# 04_POWER.net
KiCad netlist of a schematic drawn in Altium Designer
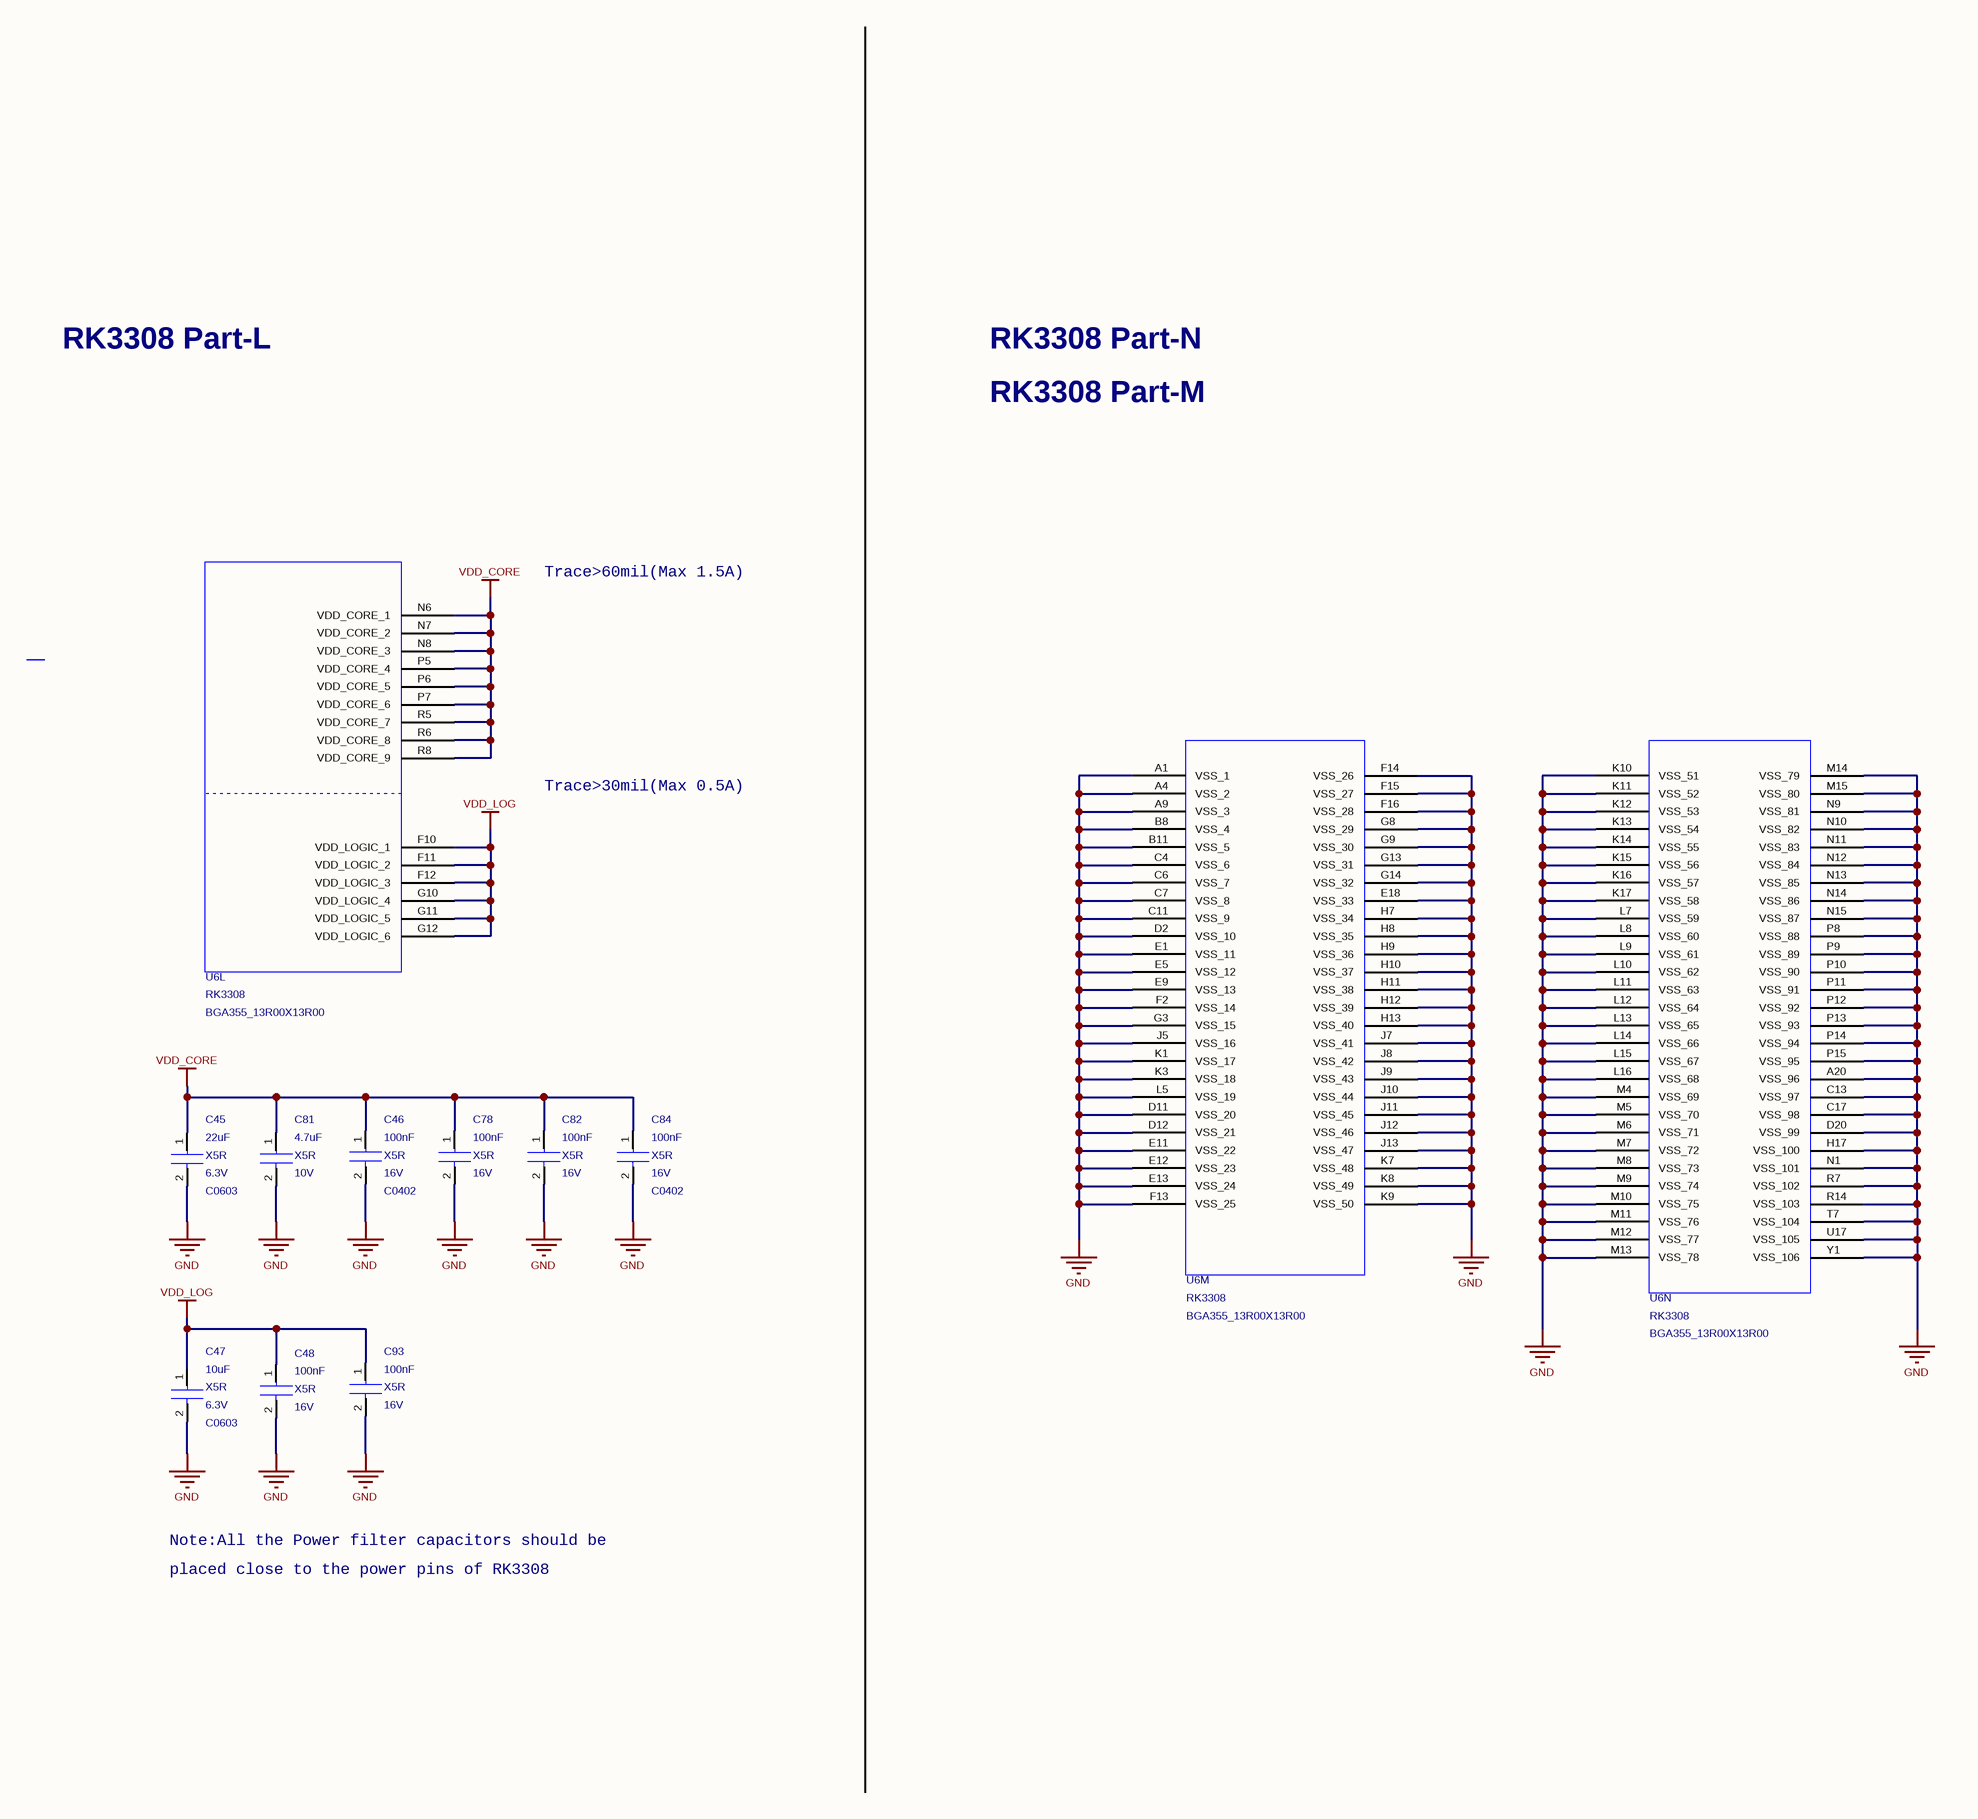
[diagram p0: 04_POWER.SchDoc]

(export (version "E")
  (design (tool "Eeschema 10.0.6"))
  (components
    (comp (ref "C45")
      (value "22uF")
      (footprint "C0603")
      (description "cap,22.00uF,+/-20%,6.3V,X5R,C0603")
      (fields
        (field (name "PCB DECAL") "C0603")
        (field (name "MANUFACTURER") "TDK")
        (field (name "TOLERANCE") "20%")
        (field (name "VOLTAGE") "6.3V")
        (field (name "DIELECTRIC") "X5R")
        (field (name "CREATED_BY") "JJJ")
      )
      (libsource (lib "*") (part "CAP_NP_2"))
    )
    (comp (ref "C46")
      (value "100nF")
      (footprint "C0402")
      (description "cap,100.00nF,+/-10%,16V,X5R,C0402")
      (fields
        (field (name "PCB DECAL") "C0402")
        (field (name "MANUFACTURER") "TDK")
        (field (name "TOLERANCE") "10%")
        (field (name "VOLTAGE") "16V")
        (field (name "DIELECTRIC") "X5R")
        (field (name "CREATED_BY") "JJJ")
      )
      (libsource (lib "*") (part "CAP_NP_2"))
    )
    (comp (ref "C47")
      (value "10uF")
      (footprint "C0603")
      (description "cap,10.00uF,+/-10%,6.3V,X5R,C0603")
      (fields
        (field (name "PCB DECAL") "C0603")
        (field (name "MANUFACTURER") "TDK")
        (field (name "TOLERANCE") "10%")
        (field (name "VOLTAGE") "6.3V")
        (field (name "DIELECTRIC") "X5R")
        (field (name "CREATED_BY") "JJJ")
      )
      (libsource (lib "*") (part "CAP_NP_2"))
    )
    (comp (ref "C48")
      (value "100nF")
      (footprint "C0402")
      (description "cap,100.00nF,+/-10%,16V,X5R,C0402")
      (fields
        (field (name "DIELECTRIC") "X5R")
        (field (name "VOLTAGE") "16V")
        (field (name "TOLERANCE") "10%")
        (field (name "MANUFACTURER") "TDK")
        (field (name "CREATED_BY") "JJJ")
      )
      (libsource (lib "*") (part "CAP_NP_2"))
    )
    (comp (ref "C78")
      (value "100nF")
      (footprint "C0402")
      (description "cap,100.00nF,+/-10%,16V,X5R,C0402")
      (fields
        (field (name "DIELECTRIC") "X5R")
        (field (name "VOLTAGE") "16V")
        (field (name "TOLERANCE") "10%")
        (field (name "MANUFACTURER") "TDK")
        (field (name "CREATED_BY") "JJJ")
      )
      (libsource (lib "*") (part "CAP_NP_2"))
    )
    (comp (ref "C81")
      (value "4.7uF")
      (footprint "C0402")
      (description "cap,4.70uF,+/-10%,10V,X5R,C0402")
      (fields
        (field (name "DIELECTRIC") "X5R")
        (field (name "VOLTAGE") "10V")
        (field (name "TOLERANCE") "10%")
        (field (name "MANUFACTURER") "TDK")
        (field (name "CREATED_BY") "JJJ")
      )
      (libsource (lib "*") (part "CAP_NP_2"))
    )
    (comp (ref "C82")
      (value "100nF")
      (footprint "C0402")
      (description "cap,100.00nF,+/-10%,16V,X5R,C0402")
      (fields
        (field (name "MANUFACTURER") "TDK")
        (field (name "TOLERANCE") "10%")
        (field (name "VOLTAGE") "16V")
        (field (name "DIELECTRIC") "X5R")
        (field (name "CREATED_BY") "JJJ")
      )
      (libsource (lib "*") (part "CAP_NP_2"))
    )
    (comp (ref "C84")
      (value "100nF")
      (footprint "C0402")
      (description "cap,100.00nF,+/-10%,16V,X5R,C0402")
      (fields
        (field (name "PCB DECAL") "C0402")
        (field (name "DIELECTRIC") "X5R")
        (field (name "VOLTAGE") "16V")
        (field (name "TOLERANCE") "10%")
        (field (name "MANUFACTURER") "TDK")
        (field (name "CREATED_BY") "JJJ")
      )
      (libsource (lib "*") (part "CAP_NP_2"))
    )
    (comp (ref "C93")
      (value "100nF")
      (footprint "C0402")
      (description "cap,100.00nF,+/-10%,16V,X5R,C0402")
      (fields
        (field (name "DIELECTRIC") "X5R")
        (field (name "VOLTAGE") "16V")
        (field (name "TOLERANCE") "10%")
        (field (name "MANUFACTURER") "TDK")
        (field (name "CREATED_BY") "JJJ")
      )
      (libsource (lib "*") (part "CAP_NP_2"))
    )
    (comp (ref "U6")
      (value "RK3308")
      (footprint "BGA355_13R00X13R00")
      (fields (field (name "PCB DECAL") "BGA355_13R00X13R00") (field (name "MANUFACTURER") "ROCKCHIP"))
      (libsource (lib "*") (part "RK3308"))
    )
  )
  (nets
    (net (code "1") (name "GND") (class "Default")
      (node (ref "C45") (pin "2") (pinfunction "2_2") (pintype "passive"))
      (node (ref "C46") (pin "2") (pinfunction "2_2") (pintype "passive"))
      (node (ref "C47") (pin "2") (pinfunction "2_2") (pintype "passive"))
      (node (ref "C48") (pin "2") (pinfunction "2_2") (pintype "passive"))
      (node (ref "C78") (pin "2") (pinfunction "2_2") (pintype "passive"))
      (node (ref "C81") (pin "2") (pinfunction "2_2") (pintype "passive"))
      (node (ref "C82") (pin "2") (pinfunction "2_2") (pintype "passive"))
      (node (ref "C84") (pin "2") (pinfunction "2_2") (pintype "passive"))
      (node (ref "C93") (pin "2") (pinfunction "2_2") (pintype "passive"))
      (node (ref "U6") (pin "A1") (pinfunction "VSS_1_A1") (pintype "power_in"))
      (node (ref "U6") (pin "A20") (pinfunction "VSS_96_A20") (pintype "power_in"))
      (node (ref "U6") (pin "A4") (pinfunction "VSS_2_A4") (pintype "power_in"))
      (node (ref "U6") (pin "A9") (pinfunction "VSS_3_A9") (pintype "power_in"))
      (node (ref "U6") (pin "B11") (pinfunction "VSS_5_B11") (pintype "power_in"))
      (node (ref "U6") (pin "B8") (pinfunction "VSS_4_B8") (pintype "power_in"))
      (node (ref "U6") (pin "C11") (pinfunction "VSS_9_C11") (pintype "power_in"))
      (node (ref "U6") (pin "C13") (pinfunction "VSS_97_C13") (pintype "power_in"))
      (node (ref "U6") (pin "C17") (pinfunction "VSS_98_C17") (pintype "power_in"))
      (node (ref "U6") (pin "C4") (pinfunction "VSS_6_C4") (pintype "power_in"))
      (node (ref "U6") (pin "C6") (pinfunction "VSS_7_C6") (pintype "power_in"))
      (node (ref "U6") (pin "C7") (pinfunction "VSS_8_C7") (pintype "power_in"))
      (node (ref "U6") (pin "D11") (pinfunction "VSS_20_D11") (pintype "power_in"))
      (node (ref "U6") (pin "D12") (pinfunction "VSS_21_D12") (pintype "power_in"))
      (node (ref "U6") (pin "D2") (pinfunction "VSS_10_D2") (pintype "power_in"))
      (node (ref "U6") (pin "D20") (pinfunction "VSS_99_D20") (pintype "power_in"))
      (node (ref "U6") (pin "E1") (pinfunction "VSS_11_E1") (pintype "power_in"))
      (node (ref "U6") (pin "E11") (pinfunction "VSS_22_E11") (pintype "power_in"))
      (node (ref "U6") (pin "E12") (pinfunction "VSS_23_E12") (pintype "power_in"))
      (node (ref "U6") (pin "E13") (pinfunction "VSS_24_E13") (pintype "power_in"))
      (node (ref "U6") (pin "E18") (pinfunction "VSS_33_E18") (pintype "power_in"))
      (node (ref "U6") (pin "E5") (pinfunction "VSS_12_E5") (pintype "power_in"))
      (node (ref "U6") (pin "E9") (pinfunction "VSS_13_E9") (pintype "power_in"))
      (node (ref "U6") (pin "F13") (pinfunction "VSS_25_F13") (pintype "power_in"))
      (node (ref "U6") (pin "F14") (pinfunction "VSS_26_F14") (pintype "power_in"))
      (node (ref "U6") (pin "F15") (pinfunction "VSS_27_F15") (pintype "power_in"))
      (node (ref "U6") (pin "F16") (pinfunction "VSS_28_F16") (pintype "power_in"))
      (node (ref "U6") (pin "F2") (pinfunction "VSS_14_F2") (pintype "power_in"))
      (node (ref "U6") (pin "G13") (pinfunction "VSS_31_G13") (pintype "power_in"))
      (node (ref "U6") (pin "G14") (pinfunction "VSS_32_G14") (pintype "power_in"))
      (node (ref "U6") (pin "G3") (pinfunction "VSS_15_G3") (pintype "power_in"))
      (node (ref "U6") (pin "G8") (pinfunction "VSS_29_G8") (pintype "power_in"))
      (node (ref "U6") (pin "G9") (pinfunction "VSS_30_G9") (pintype "power_in"))
      (node (ref "U6") (pin "H10") (pinfunction "VSS_37_H10") (pintype "power_in"))
      (node (ref "U6") (pin "H11") (pinfunction "VSS_38_H11") (pintype "power_in"))
      (node (ref "U6") (pin "H12") (pinfunction "VSS_39_H12") (pintype "power_in"))
      (node (ref "U6") (pin "H13") (pinfunction "VSS_40_H13") (pintype "power_in"))
      (node (ref "U6") (pin "H17") (pinfunction "VSS_100_H17") (pintype "power_in"))
      (node (ref "U6") (pin "H7") (pinfunction "VSS_34_H7") (pintype "power_in"))
      (node (ref "U6") (pin "H8") (pinfunction "VSS_35_H8") (pintype "power_in"))
      (node (ref "U6") (pin "H9") (pinfunction "VSS_36_H9") (pintype "power_in"))
      (node (ref "U6") (pin "J10") (pinfunction "VSS_44_J10") (pintype "power_in"))
      (node (ref "U6") (pin "J11") (pinfunction "VSS_45_J11") (pintype "power_in"))
      (node (ref "U6") (pin "J12") (pinfunction "VSS_46_J12") (pintype "power_in"))
      (node (ref "U6") (pin "J13") (pinfunction "VSS_47_J13") (pintype "power_in"))
      (node (ref "U6") (pin "J5") (pinfunction "VSS_16_J5") (pintype "power_in"))
      (node (ref "U6") (pin "J7") (pinfunction "VSS_41_J7") (pintype "power_in"))
      (node (ref "U6") (pin "J8") (pinfunction "VSS_42_J8") (pintype "power_in"))
      (node (ref "U6") (pin "J9") (pinfunction "VSS_43_J9") (pintype "power_in"))
      (node (ref "U6") (pin "K1") (pinfunction "VSS_17_K1") (pintype "power_in"))
      (node (ref "U6") (pin "K10") (pinfunction "VSS_51_K10") (pintype "power_in"))
      (node (ref "U6") (pin "K11") (pinfunction "VSS_52_K11") (pintype "power_in"))
      (node (ref "U6") (pin "K12") (pinfunction "VSS_53_K12") (pintype "power_in"))
      (node (ref "U6") (pin "K13") (pinfunction "VSS_54_K13") (pintype "power_in"))
      (node (ref "U6") (pin "K14") (pinfunction "VSS_55_K14") (pintype "power_in"))
      (node (ref "U6") (pin "K15") (pinfunction "VSS_56_K15") (pintype "power_in"))
      (node (ref "U6") (pin "K16") (pinfunction "VSS_57_K16") (pintype "power_in"))
      (node (ref "U6") (pin "K17") (pinfunction "VSS_58_K17") (pintype "power_in"))
      (node (ref "U6") (pin "K3") (pinfunction "VSS_18_K3") (pintype "power_in"))
      (node (ref "U6") (pin "K7") (pinfunction "VSS_48_K7") (pintype "power_in"))
      (node (ref "U6") (pin "K8") (pinfunction "VSS_49_K8") (pintype "power_in"))
      (node (ref "U6") (pin "K9") (pinfunction "VSS_50_K9") (pintype "power_in"))
      (node (ref "U6") (pin "L10") (pinfunction "VSS_62_L10") (pintype "power_in"))
      (node (ref "U6") (pin "L11") (pinfunction "VSS_63_L11") (pintype "power_in"))
      (node (ref "U6") (pin "L12") (pinfunction "VSS_64_L12") (pintype "power_in"))
      (node (ref "U6") (pin "L13") (pinfunction "VSS_65_L13") (pintype "power_in"))
      (node (ref "U6") (pin "L14") (pinfunction "VSS_66_L14") (pintype "power_in"))
      (node (ref "U6") (pin "L15") (pinfunction "VSS_67_L15") (pintype "power_in"))
      (node (ref "U6") (pin "L16") (pinfunction "VSS_68_L16") (pintype "power_in"))
      (node (ref "U6") (pin "L5") (pinfunction "VSS_19_L5") (pintype "power_in"))
      (node (ref "U6") (pin "L7") (pinfunction "VSS_59_L7") (pintype "power_in"))
      (node (ref "U6") (pin "L8") (pinfunction "VSS_60_L8") (pintype "power_in"))
      (node (ref "U6") (pin "L9") (pinfunction "VSS_61_L9") (pintype "power_in"))
      (node (ref "U6") (pin "M10") (pinfunction "VSS_75_M10") (pintype "power_in"))
      (node (ref "U6") (pin "M11") (pinfunction "VSS_76_M11") (pintype "power_in"))
      (node (ref "U6") (pin "M12") (pinfunction "VSS_77_M12") (pintype "power_in"))
      (node (ref "U6") (pin "M13") (pinfunction "VSS_78_M13") (pintype "power_in"))
      (node (ref "U6") (pin "M14") (pinfunction "VSS_79_M14") (pintype "power_in"))
      (node (ref "U6") (pin "M15") (pinfunction "VSS_80_M15") (pintype "power_in"))
      (node (ref "U6") (pin "M4") (pinfunction "VSS_69_M4") (pintype "power_in"))
      (node (ref "U6") (pin "M5") (pinfunction "VSS_70_M5") (pintype "power_in"))
      (node (ref "U6") (pin "M6") (pinfunction "VSS_71_M6") (pintype "power_in"))
      (node (ref "U6") (pin "M7") (pinfunction "VSS_72_M7") (pintype "power_in"))
      (node (ref "U6") (pin "M8") (pinfunction "VSS_73_M8") (pintype "power_in"))
      (node (ref "U6") (pin "M9") (pinfunction "VSS_74_M9") (pintype "power_in"))
      (node (ref "U6") (pin "N1") (pinfunction "VSS_101_N1") (pintype "power_in"))
      (node (ref "U6") (pin "N10") (pinfunction "VSS_82_N10") (pintype "power_in"))
      (node (ref "U6") (pin "N11") (pinfunction "VSS_83_N11") (pintype "power_in"))
      (node (ref "U6") (pin "N12") (pinfunction "VSS_84_N12") (pintype "power_in"))
      (node (ref "U6") (pin "N13") (pinfunction "VSS_85_N13") (pintype "power_in"))
      (node (ref "U6") (pin "N14") (pinfunction "VSS_86_N14") (pintype "power_in"))
      (node (ref "U6") (pin "N15") (pinfunction "VSS_87_N15") (pintype "power_in"))
      (node (ref "U6") (pin "N9") (pinfunction "VSS_81_N9") (pintype "power_in"))
      (node (ref "U6") (pin "P10") (pinfunction "VSS_90_P10") (pintype "power_in"))
      (node (ref "U6") (pin "P11") (pinfunction "VSS_91_P11") (pintype "power_in"))
      (node (ref "U6") (pin "P12") (pinfunction "VSS_92_P12") (pintype "power_in"))
      (node (ref "U6") (pin "P13") (pinfunction "VSS_93_P13") (pintype "power_in"))
      (node (ref "U6") (pin "P14") (pinfunction "VSS_94_P14") (pintype "power_in"))
      (node (ref "U6") (pin "P15") (pinfunction "VSS_95_P15") (pintype "power_in"))
      (node (ref "U6") (pin "P8") (pinfunction "VSS_88_P8") (pintype "power_in"))
      (node (ref "U6") (pin "P9") (pinfunction "VSS_89_P9") (pintype "power_in"))
      (node (ref "U6") (pin "R14") (pinfunction "VSS_103_R14") (pintype "power_in"))
      (node (ref "U6") (pin "R7") (pinfunction "VSS_102_R7") (pintype "power_in"))
      (node (ref "U6") (pin "T7") (pinfunction "VSS_104_T7") (pintype "power_in"))
      (node (ref "U6") (pin "U17") (pinfunction "VSS_105_U17") (pintype "power_in"))
      (node (ref "U6") (pin "Y1") (pinfunction "VSS_106_Y1") (pintype "power_in"))
    )
    (net (code "2") (name "VDD_CORE") (class "Default")
      (node (ref "C45") (pin "1") (pinfunction "1_1") (pintype "passive"))
      (node (ref "C46") (pin "1") (pinfunction "1_1") (pintype "passive"))
      (node (ref "C78") (pin "1") (pinfunction "1_1") (pintype "passive"))
      (node (ref "C81") (pin "1") (pinfunction "1_1") (pintype "passive"))
      (node (ref "C82") (pin "1") (pinfunction "1_1") (pintype "passive"))
      (node (ref "C84") (pin "1") (pinfunction "1_1") (pintype "passive"))
      (node (ref "U6") (pin "N6") (pinfunction "VDD_CORE_1_N6") (pintype "power_in"))
      (node (ref "U6") (pin "N7") (pinfunction "VDD_CORE_2_N7") (pintype "power_in"))
      (node (ref "U6") (pin "N8") (pinfunction "VDD_CORE_3_N8") (pintype "power_in"))
      (node (ref "U6") (pin "P5") (pinfunction "VDD_CORE_4_P5") (pintype "power_in"))
      (node (ref "U6") (pin "P6") (pinfunction "VDD_CORE_5_P6") (pintype "power_in"))
      (node (ref "U6") (pin "P7") (pinfunction "VDD_CORE_6_P7") (pintype "power_in"))
      (node (ref "U6") (pin "R5") (pinfunction "VDD_CORE_7_R5") (pintype "power_in"))
      (node (ref "U6") (pin "R6") (pinfunction "VDD_CORE_8_R6") (pintype "power_in"))
      (node (ref "U6") (pin "R8") (pinfunction "VDD_CORE_9_R8") (pintype "power_in"))
    )
    (net (code "3") (name "VDD_LOG") (class "Default")
      (node (ref "C47") (pin "1") (pinfunction "1_1") (pintype "passive"))
      (node (ref "C48") (pin "1") (pinfunction "1_1") (pintype "passive"))
      (node (ref "C93") (pin "1") (pinfunction "1_1") (pintype "passive"))
      (node (ref "U6") (pin "F10") (pinfunction "VDD_LOGIC_1_F10") (pintype "power_in"))
      (node (ref "U6") (pin "F11") (pinfunction "VDD_LOGIC_2_F11") (pintype "power_in"))
      (node (ref "U6") (pin "F12") (pinfunction "VDD_LOGIC_3_F12") (pintype "power_in"))
      (node (ref "U6") (pin "G10") (pinfunction "VDD_LOGIC_4_G10") (pintype "power_in"))
      (node (ref "U6") (pin "G11") (pinfunction "VDD_LOGIC_5_G11") (pintype "power_in"))
      (node (ref "U6") (pin "G12") (pinfunction "VDD_LOGIC_6_G12") (pintype "power_in"))
    )
  )
)
